# Load_Switch.net
KiCad netlist of a schematic drawn in EAGLE
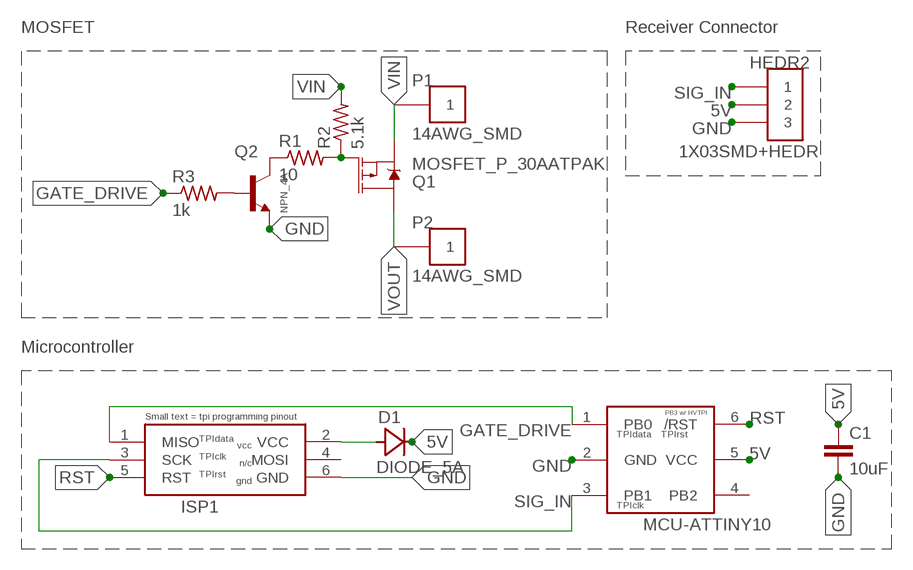
[diagram p0: schematic, sheet 1]

(export (version "E")
  (design (tool "Eeschema 10.0.6"))
  (components
    (comp (ref "C1")
      (value "10uF")
      (footprint "eagle-import:1206")
      (libsource (lib "eagle-import") (part "10UF-1206-6.3V-20%"))
    )
    (comp (ref "D1")
      (value "DIODE_5A")
      (footprint "eagle-import:DO-214AC")
      (libsource (lib "eagle-import") (part "DIODE_5A"))
    )
    (comp (ref "HEDR2")
      (value "1X03SMD+HEDR")
      (footprint "eagle-import:1X3_SMD+HEDR")
      (libsource (lib "eagle-import") (part "1X03SMD+HEDR"))
    )
    (comp (ref "IC1")
      (value "MCU-ATTINY10")
      (footprint "eagle-import:SOT23-6")
      (libsource (lib "eagle-import") (part "MCU-ATTINY10"))
    )
    (comp (ref "ISP1")
      (value "CON-ICSP/ISP-AVR-POGO")
      (footprint "eagle-import:2X3_POGO_AVR")
      (libsource (lib "eagle-import") (part "CON-ICSP/ISP-AVR-POGO"))
    )
    (comp (ref "P1")
      (value "14AWG_SMD")
      (footprint "eagle-import:14AWG_PAD")
      (libsource (lib "eagle-import") (part "14AWG_SMD"))
    )
    (comp (ref "P2")
      (value "14AWG_SMD")
      (footprint "eagle-import:14AWG_PAD")
      (libsource (lib "eagle-import") (part "14AWG_SMD"))
    )
    (comp (ref "Q1")
      (value "MOSFET_P_30AATPAK")
      (footprint "eagle-import:TO-252_DPAK")
      (libsource (lib "eagle-import") (part "MOSFET_P_30AATPAK"))
    )
    (comp (ref "Q2")
      (value "NPN_4A")
      (footprint "eagle-import:SOT23-3")
      (libsource (lib "eagle-import") (part "NPN_4A"))
    )
    (comp (ref "R1")
      (value "10")
      (footprint "eagle-import:TG-0603")
      (libsource (lib "eagle-import") (part "R_TG_0603"))
    )
    (comp (ref "R2")
      (value "5.1k")
      (footprint "eagle-import:TG-0603")
      (libsource (lib "eagle-import") (part "R_TG_0603"))
    )
    (comp (ref "R3")
      (value "1k")
      (footprint "eagle-import:TG-0603")
      (libsource (lib "eagle-import") (part "R_TG_0603"))
    )
  )
  (nets
    (net (code "1") (name "/SIG_IN") (class "Default")
      (node (ref "HEDR2") (pin "1") (pinfunction "1_1") (pintype "bidirectional"))
      (node (ref "IC1") (pin "3") (pinfunction "PB1_3") (pintype "bidirectional"))
      (node (ref "ISP1") (pin "3") (pinfunction "SCK_3") (pintype "output"))
    )
    (net (code "2") (name "5V") (class "Default")
      (node (ref "C1") (pin "1") (pinfunction "1_1") (pintype "passive"))
      (node (ref "D1") (pin "1") (pinfunction "C_1") (pintype "passive"))
      (node (ref "HEDR2") (pin "2") (pinfunction "2_2") (pintype "bidirectional"))
      (node (ref "IC1") (pin "5") (pinfunction "VCC_5") (pintype "power_in"))
    )
    (net (code "3") (name "GATE_DRIVE") (class "Default")
      (node (ref "IC1") (pin "1") (pinfunction "PB0_1") (pintype "bidirectional"))
      (node (ref "ISP1") (pin "1") (pinfunction "MISO_1") (pintype "input"))
      (node (ref "R3") (pin "1") (pinfunction "1_1") (pintype "passive"))
    )
    (net (code "4") (name "GND") (class "Default")
      (node (ref "C1") (pin "2") (pinfunction "2_2") (pintype "passive"))
      (node (ref "HEDR2") (pin "3") (pinfunction "3_3") (pintype "bidirectional"))
      (node (ref "IC1") (pin "2") (pinfunction "GND_2") (pintype "power_in"))
      (node (ref "ISP1") (pin "6") (pinfunction "GND_6") (pintype "power_in"))
      (node (ref "Q2") (pin "2") (pinfunction "E_2") (pintype "passive"))
    )
    (net (code "5") (name "Net-(D1-A)") (class "Default")
      (node (ref "D1") (pin "2") (pinfunction "A_2") (pintype "passive"))
      (node (ref "ISP1") (pin "2") (pinfunction "VCC_2") (pintype "power_in"))
    )
    (net (code "6") (name "Net-(Q1-G)") (class "Default")
      (node (ref "Q1") (pin "1") (pinfunction "G_1") (pintype "bidirectional"))
      (node (ref "R1") (pin "2") (pinfunction "2_2") (pintype "passive"))
      (node (ref "R2") (pin "1") (pinfunction "1_1") (pintype "passive"))
    )
    (net (code "7") (name "Net-(Q2-B)") (class "Default")
      (node (ref "Q2") (pin "1") (pinfunction "B_1") (pintype "passive"))
      (node (ref "R3") (pin "2") (pinfunction "2_2") (pintype "passive"))
    )
    (net (code "8") (name "Net-(Q2-C)") (class "Default")
      (node (ref "Q2") (pin "3") (pinfunction "C_3") (pintype "passive"))
      (node (ref "R1") (pin "1") (pinfunction "1_1") (pintype "passive"))
    )
    (net (code "9") (name "RST") (class "Default")
      (node (ref "IC1") (pin "6") (pinfunction "/RST_6") (pintype "bidirectional"))
      (node (ref "ISP1") (pin "5") (pinfunction "RST_5") (pintype "output"))
    )
    (net (code "10") (name "VIN") (class "Default")
      (node (ref "P1") (pin "PAD") (pinfunction "1_PAD") (pintype "bidirectional"))
      (node (ref "Q1") (pin "3") (pinfunction "S_3") (pintype "bidirectional"))
      (node (ref "R2") (pin "2") (pinfunction "2_2") (pintype "passive"))
    )
    (net (code "11") (name "VOUT") (class "Default")
      (node (ref "P2") (pin "PAD") (pinfunction "1_PAD") (pintype "bidirectional"))
      (node (ref "Q1") (pin "2") (pinfunction "D_2") (pintype "bidirectional"))
    )
    (net (code "12") (name "unconnected-(IC1-PB2-Pad4)") (class "Default")
      (node (ref "IC1") (pin "4") (pinfunction "PB2_4") (pintype "bidirectional"))
    )
    (net (code "13") (name "unconnected-(ISP1-MOSI-Pad4)") (class "Default")
      (node (ref "ISP1") (pin "4") (pinfunction "MOSI_4") (pintype "output"))
    )
  )
)
